# oled.net
KiCad netlist of a schematic drawn in EAGLE
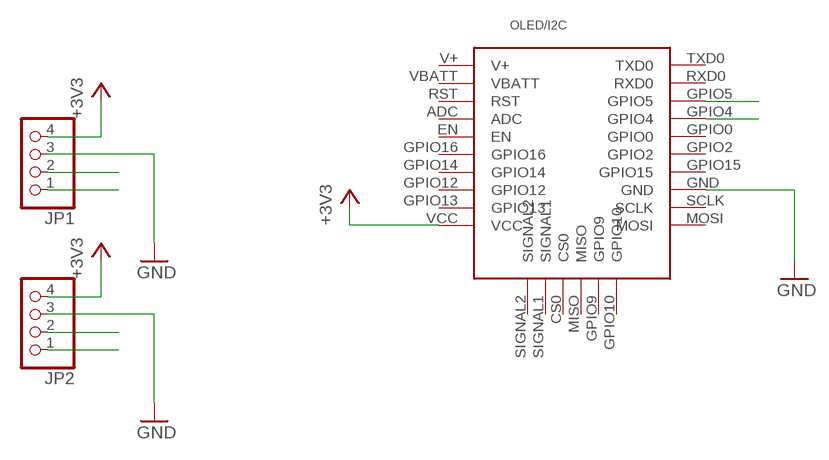
[diagram p0: schematic, sheet 1]

(export (version "E")
  (design (tool "Eeschema 10.0.6"))
  (components
    (comp (ref "JP1")
      (value "PINHD-1X4")
      (footprint "eagle-import:1X04")
      (libsource (lib "eagle-import") (part "PINHD-1X4"))
    )
    (comp (ref "JP2")
      (value "PINHD-1X4")
      (footprint "eagle-import:1X04")
      (libsource (lib "eagle-import") (part "PINHD-1X4"))
    )
    (comp (ref "OLED/I2C")
      (value "ESP-BOARD")
      (footprint "eagle-import:ESP-BOARD")
      (libsource (lib "eagle-import") (part "ESP-BOARD"))
    )
  )
  (nets
    (net (code "1") (name "+3V3") (class "Default")
      (node (ref "JP1") (pin "4") (pinfunction "4_4") (pintype "passive"))
      (node (ref "JP2") (pin "4") (pinfunction "4_4") (pintype "passive"))
      (node (ref "OLED/I2C") (pin "VCC") (pinfunction "VCC_VCC") (pintype "power_in"))
    )
    (net (code "2") (name "/SCL") (class "Default")
      (node (ref "JP1") (pin "2") (pinfunction "2_2") (pintype "passive"))
      (node (ref "JP2") (pin "2") (pinfunction "2_2") (pintype "passive"))
      (node (ref "OLED/I2C") (pin "GPIO5") (pinfunction "GPIO5_GPIO5") (pintype "bidirectional"))
    )
    (net (code "3") (name "/SDA") (class "Default")
      (node (ref "JP1") (pin "1") (pinfunction "1_1") (pintype "passive"))
      (node (ref "JP2") (pin "1") (pinfunction "1_1") (pintype "passive"))
      (node (ref "OLED/I2C") (pin "GPIO4") (pinfunction "GPIO4_GPIO4") (pintype "bidirectional"))
    )
    (net (code "4") (name "/V+") (class "Default")
      (node (ref "OLED/I2C") (pin "V+") (pinfunction "V+_V+") (pintype "power_in"))
    )
    (net (code "5") (name "/VBATT") (class "Default")
      (node (ref "OLED/I2C") (pin "VBATT") (pinfunction "VBATT_VBATT") (pintype "power_in"))
    )
    (net (code "6") (name "GND") (class "Default")
      (node (ref "JP1") (pin "3") (pinfunction "3_3") (pintype "passive"))
      (node (ref "JP2") (pin "3") (pinfunction "3_3") (pintype "passive"))
      (node (ref "OLED/I2C") (pin "GND") (pinfunction "GND_GND") (pintype "power_in"))
    )
    (net (code "7") (name "unconnected-(OLED/I2C-PadADC)") (class "Default")
      (node (ref "OLED/I2C") (pin "ADC") (pinfunction "ADC_ADC") (pintype "bidirectional"))
    )
    (net (code "8") (name "unconnected-(OLED/I2C-PadCS0)") (class "Default")
      (node (ref "OLED/I2C") (pin "CS0") (pinfunction "CS0_CS0") (pintype "bidirectional"))
    )
    (net (code "9") (name "unconnected-(OLED/I2C-PadEN)") (class "Default")
      (node (ref "OLED/I2C") (pin "EN") (pinfunction "EN_EN") (pintype "bidirectional"))
    )
    (net (code "10") (name "unconnected-(OLED/I2C-PadGPIO0)") (class "Default")
      (node (ref "OLED/I2C") (pin "GPIO0") (pinfunction "GPIO0_GPIO0") (pintype "bidirectional"))
    )
    (net (code "11") (name "unconnected-(OLED/I2C-PadGPIO2)") (class "Default")
      (node (ref "OLED/I2C") (pin "GPIO2") (pinfunction "GPIO2_GPIO2") (pintype "bidirectional"))
    )
    (net (code "12") (name "unconnected-(OLED/I2C-PadGPIO9)") (class "Default")
      (node (ref "OLED/I2C") (pin "GPIO9") (pinfunction "GPIO9_GPIO9") (pintype "bidirectional"))
    )
    (net (code "13") (name "unconnected-(OLED/I2C-PadGPIO10)") (class "Default")
      (node (ref "OLED/I2C") (pin "GPIO10") (pinfunction "GPIO10_GPIO10") (pintype "bidirectional"))
    )
    (net (code "14") (name "unconnected-(OLED/I2C-PadGPIO12)") (class "Default")
      (node (ref "OLED/I2C") (pin "GPIO12") (pinfunction "GPIO12_GPIO12") (pintype "bidirectional"))
    )
    (net (code "15") (name "unconnected-(OLED/I2C-PadGPIO13)") (class "Default")
      (node (ref "OLED/I2C") (pin "GPIO13") (pinfunction "GPIO13_GPIO13") (pintype "bidirectional"))
    )
    (net (code "16") (name "unconnected-(OLED/I2C-PadGPIO14)") (class "Default")
      (node (ref "OLED/I2C") (pin "GPIO14") (pinfunction "GPIO14_GPIO14") (pintype "bidirectional"))
    )
    (net (code "17") (name "unconnected-(OLED/I2C-PadGPIO15)") (class "Default")
      (node (ref "OLED/I2C") (pin "GPIO15") (pinfunction "GPIO15_GPIO15") (pintype "bidirectional"))
    )
    (net (code "18") (name "unconnected-(OLED/I2C-PadGPIO16)") (class "Default")
      (node (ref "OLED/I2C") (pin "GPIO16") (pinfunction "GPIO16_GPIO16") (pintype "bidirectional"))
    )
    (net (code "19") (name "unconnected-(OLED/I2C-PadMISO)") (class "Default")
      (node (ref "OLED/I2C") (pin "MISO") (pinfunction "MISO_MISO") (pintype "bidirectional"))
    )
    (net (code "20") (name "unconnected-(OLED/I2C-PadMOSI)") (class "Default")
      (node (ref "OLED/I2C") (pin "MOSI") (pinfunction "MOSI_MOSI") (pintype "bidirectional"))
    )
    (net (code "21") (name "unconnected-(OLED/I2C-PadRST)") (class "Default")
      (node (ref "OLED/I2C") (pin "RST") (pinfunction "RST_RST") (pintype "bidirectional"))
    )
    (net (code "22") (name "unconnected-(OLED/I2C-PadRXD0)") (class "Default")
      (node (ref "OLED/I2C") (pin "RXD0") (pinfunction "RXD0_RXD0") (pintype "bidirectional"))
    )
    (net (code "23") (name "unconnected-(OLED/I2C-PadSCLK)") (class "Default")
      (node (ref "OLED/I2C") (pin "SCLK") (pinfunction "SCLK_SCLK") (pintype "bidirectional"))
    )
    (net (code "24") (name "unconnected-(OLED/I2C-PadSIGNAL1)") (class "Default")
      (node (ref "OLED/I2C") (pin "SIGNAL1") (pinfunction "SIGNAL1_SIGNAL1") (pintype "bidirectional"))
    )
    (net (code "25") (name "unconnected-(OLED/I2C-PadSIGNAL2)") (class "Default")
      (node (ref "OLED/I2C") (pin "SIGNAL2") (pinfunction "SIGNAL2_SIGNAL2") (pintype "bidirectional"))
    )
    (net (code "26") (name "unconnected-(OLED/I2C-PadTXD0)") (class "Default")
      (node (ref "OLED/I2C") (pin "TXD0") (pinfunction "TXD0_TXD0") (pintype "bidirectional"))
    )
  )
)
